# POWER.net
KiCad netlist of a schematic drawn in Altium Designer
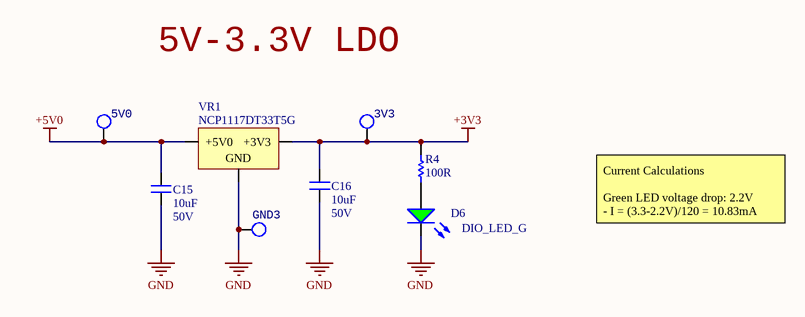
[diagram p0: POWER.SchDoc]

(export (version "E")
  (design (tool "Eeschema 10.0.6"))
  (components
    (comp (ref "3V3")
      (value "TESTPOINT_LOOP")
      (footprint "TESTPOINT_LOOP")
      (description "Loop testpoint through-hole pad")
      (fields (field (name "MANUFACTURER") "Keystone Electronics"))
      (libsource (lib "UWRT_Schematic_Library_2020") (part "TESTPOINT_LOOP"))
    )
    (comp (ref "5V0")
      (value "TESTPOINT_LOOP")
      (footprint "TESTPOINT_LOOP")
      (description "Loop testpoint through-hole pad")
      (fields (field (name "MANUFACTURER") "Keystone Electronics"))
      (libsource (lib "UWRT_Schematic_Library_2020") (part "TESTPOINT_LOOP"))
    )
    (comp (ref "C15")
      (value "10uF")
      (footprint "CAPC1206(3216)")
      (description "CAP CER 10UF 50V X5R 1206")
      (fields
        (field (name "MPN") "GRT31CR61H106KE01L")
        (field (name "MANUFACTURER") "Murata")
        (field (name "VOLTAGE RATING") "50V")
      )
      (libsource (lib "UWRT_Schematic_Library_2020") (part "CAP_10uF_50V_1206"))
    )
    (comp (ref "C16")
      (value "10uF")
      (footprint "CAPC1206(3216)")
      (description "CAP CER 10UF 50V X5R 1206")
      (fields
        (field (name "MPN") "GRT31CR61H106KE01L")
        (field (name "MANUFACTURER") "Murata")
        (field (name "VOLTAGE RATING") "50V")
      )
      (libsource (lib "UWRT_Schematic_Library_2020") (part "CAP_10uF_50V_1206"))
    )
    (comp (ref "D6")
      (value "DIO_LED_G")
      (footprint "LED_0805_LINE")
      (description "LED GREEN DIFFUSED 0805 SMD")
      (fields (field (name "MPN") "LG R971-KN-1") (field (name "MANUFACTURER") "OSRAM"))
      (libsource (lib "UWRT_Schematic_Library_2020") (part "DIO_LED_G"))
    )
    (comp (ref "GND3")
      (value "TESTPOINT_LOOP")
      (footprint "TESTPOINT_LOOP")
      (description "Loop testpoint through-hole pad")
      (fields (field (name "MANUFACTURER") "Keystone Electronics"))
      (libsource (lib "UWRT_Schematic_Library_2020") (part "TESTPOINT_LOOP"))
    )
    (comp (ref "R4")
      (value "100R")
      (footprint "RESC0603(1608)_N")
      (description "RES SMD 100 OHM 1% 1/10W 0603")
      (fields (field (name "MANUFACTURER") "Yageo") (field (name "MPN") "RC0603FR-07100RL"))
      (libsource (lib "UWRT_Schematic_Library_2020") (part "RES_100R_0603"))
    )
    (comp (ref "VR1")
      (value "5V0_3V3_LDO")
      (footprint "VOLTAGE_REGULATOR")
      (description "IC REG LINEAR 3.3V 1A DPAK")
      (fields (field (name "MPN") "NCP1117DT33T5G") (field (name "MANUFACTURER") "ON Semiconductor"))
      (libsource (lib "UWRT_Schematic_Library_2020") (part "5V0_3V3_LDO"))
    )
  )
  (nets
    (net (code "1") (name "+3V3") (class "Default")
      (node (ref "3V3") (pin "1") (pintype "passive"))
      (node (ref "C16") (pin "1") (pinfunction "1_1") (pintype "passive"))
      (node (ref "R4") (pin "2") (pinfunction "2_2") (pintype "passive"))
      (node (ref "VR1") (pin "2") (pinfunction "+3V3_2") (pintype "passive"))
    )
    (net (code "2") (name "+5V0") (class "Default")
      (node (ref "5V0") (pin "1") (pintype "passive"))
      (node (ref "C15") (pin "1") (pinfunction "1_1") (pintype "passive"))
      (node (ref "VR1") (pin "3") (pinfunction "+5V0_3") (pintype "passive"))
    )
    (net (code "3") (name "GND") (class "Default")
      (node (ref "C15") (pin "2") (pinfunction "2_2") (pintype "passive"))
      (node (ref "C16") (pin "2") (pinfunction "2_2") (pintype "passive"))
      (node (ref "D6") (pin "2") (pinfunction "K_2") (pintype "passive"))
      (node (ref "GND3") (pin "1") (pintype "passive"))
      (node (ref "VR1") (pin "1") (pinfunction "GND_1") (pintype "passive"))
    )
    (net (code "4") (name "Net-(D6-A)") (class "Default")
      (node (ref "D6") (pin "1") (pinfunction "A_1") (pintype "passive"))
      (node (ref "R4") (pin "1") (pinfunction "1_1") (pintype "passive"))
    )
  )
)
